# seeeduino_nano.net
KiCad netlist of a schematic drawn in EAGLE
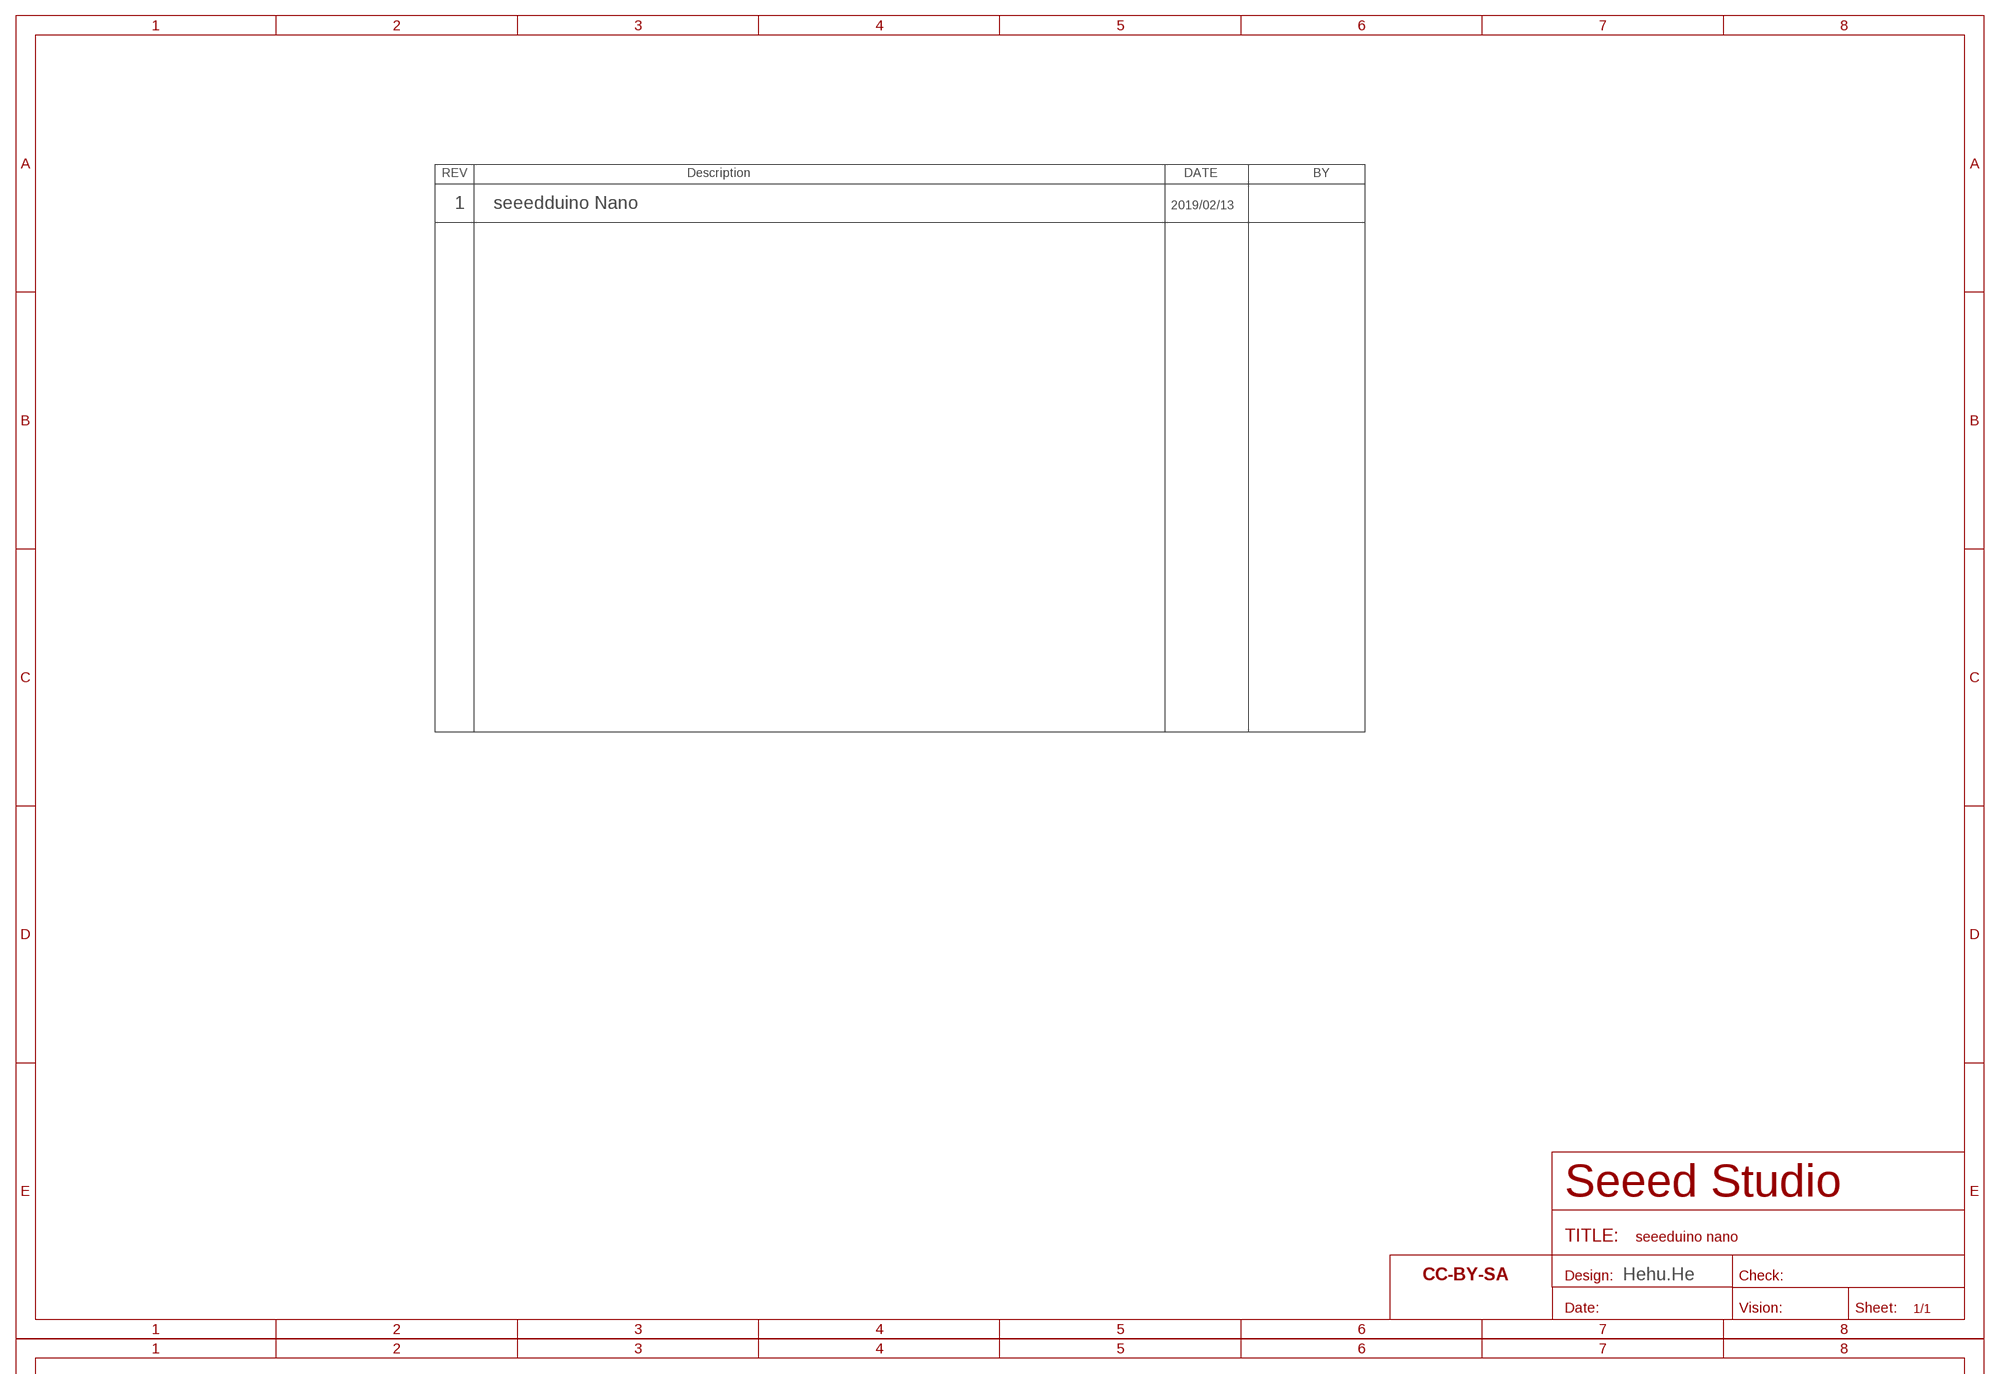
[diagram p0: schematic, sheet 1, part 1 of 2]
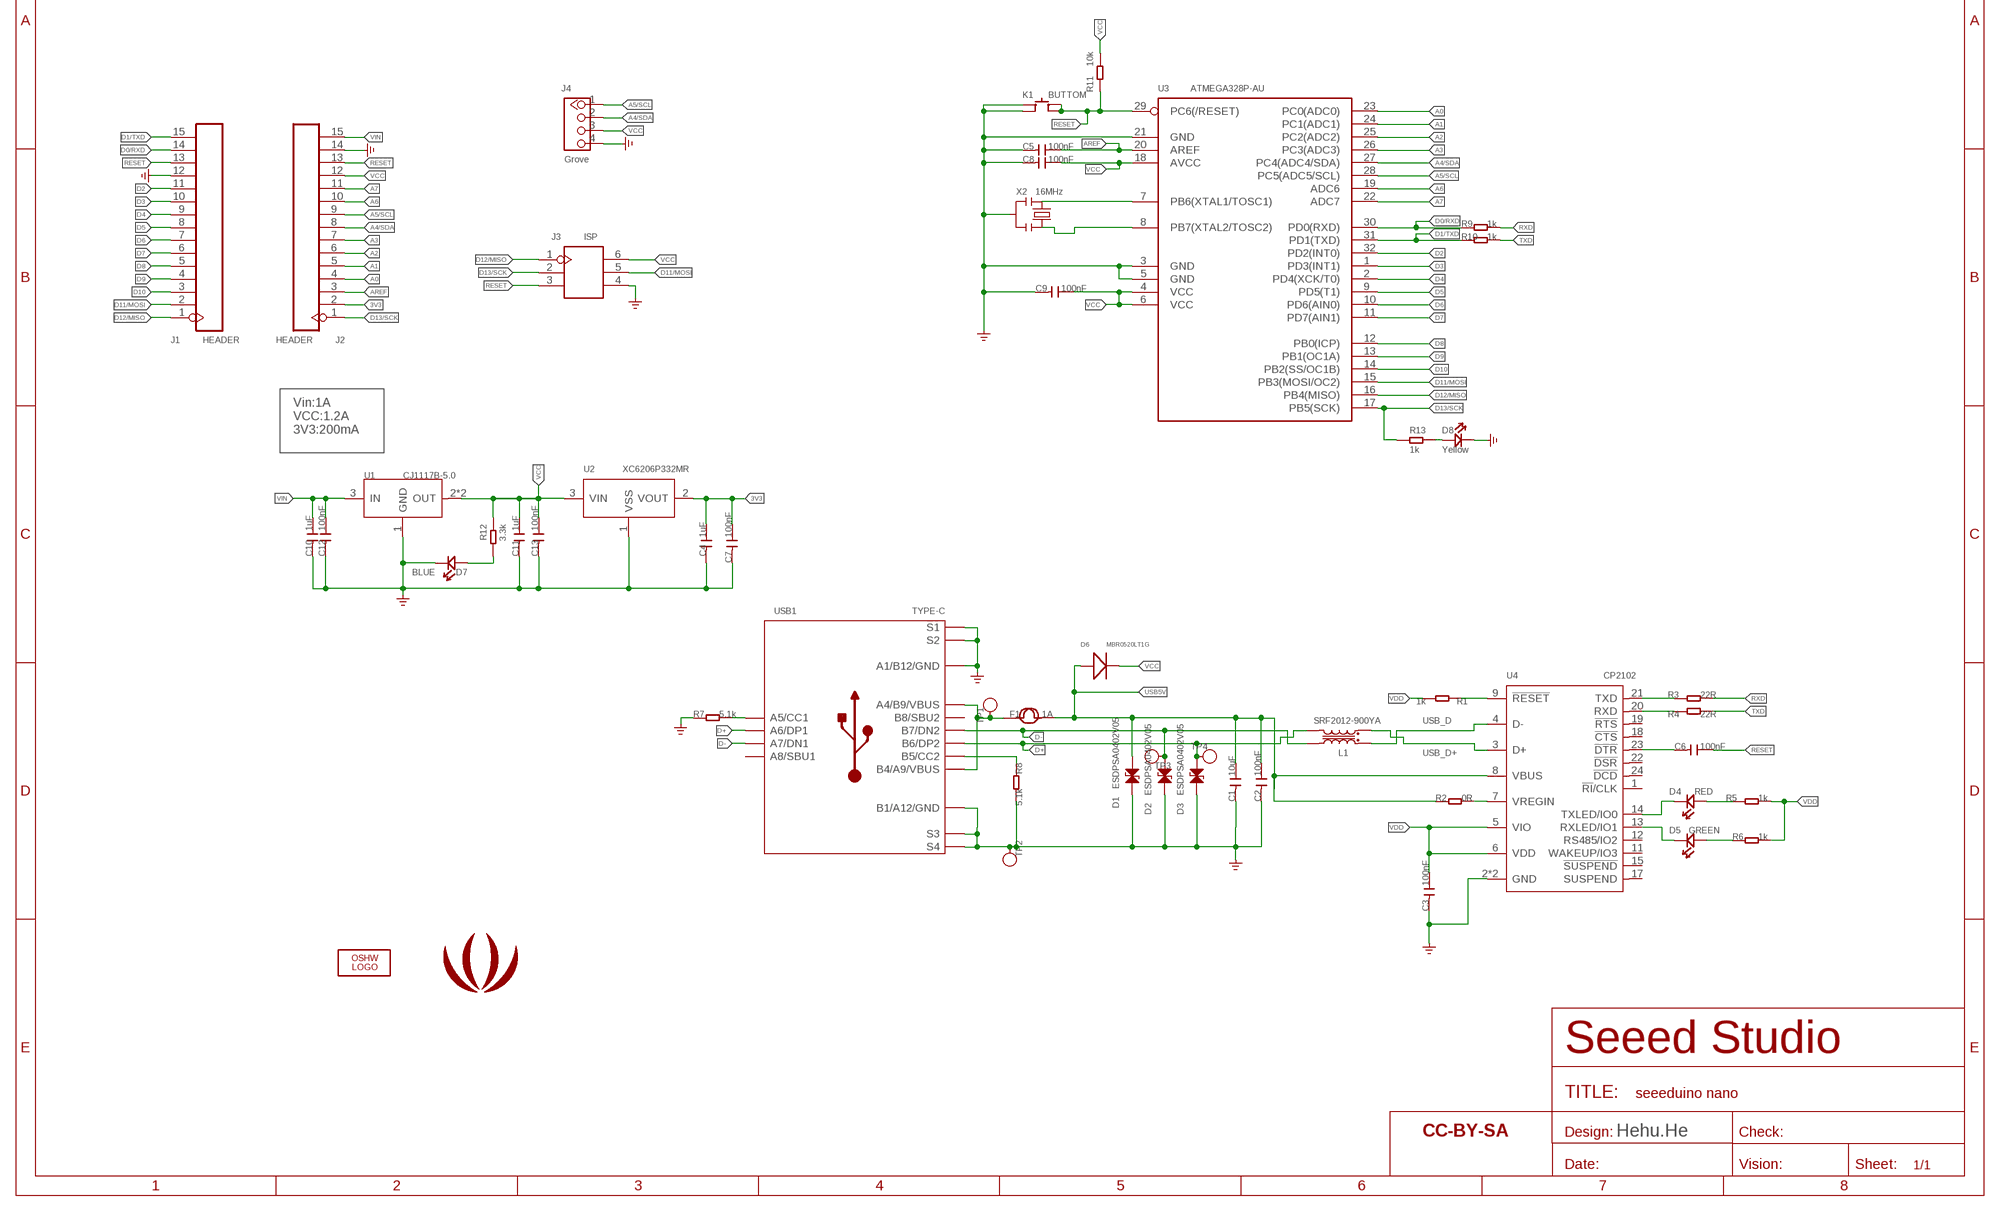
[diagram p1: schematic, sheet 1, part 2 of 2]

(export (version "E")
  (design (tool "Eeschema 10.0.6"))
  (components
    (comp (ref "C1")
      (value "10uF")
      (footprint "eagle-import:C0603")
      (libsource (lib "eagle-import") (part "CAP-0603"))
    )
    (comp (ref "C2")
      (value "100nF")
      (footprint "eagle-import:C0603")
      (libsource (lib "eagle-import") (part "CAP-0603"))
    )
    (comp (ref "C3")
      (value "100nF")
      (footprint "eagle-import:C0603")
      (libsource (lib "eagle-import") (part "C-0603"))
    )
    (comp (ref "C4")
      (value "1uF")
      (footprint "eagle-import:C0603")
      (libsource (lib "eagle-import") (part "C-0603"))
    )
    (comp (ref "C5")
      (value "100nF")
      (footprint "eagle-import:C0603")
      (libsource (lib "eagle-import") (part "C-0603"))
    )
    (comp (ref "C6")
      (value "100nF")
      (footprint "eagle-import:C0603")
      (libsource (lib "eagle-import") (part "C-0603"))
    )
    (comp (ref "C7")
      (value "100nF")
      (footprint "eagle-import:C0603")
      (libsource (lib "eagle-import") (part "C-0603"))
    )
    (comp (ref "C8")
      (value "100nF")
      (footprint "eagle-import:C0603")
      (libsource (lib "eagle-import") (part "C-0603"))
    )
    (comp (ref "C9")
      (value "100nF")
      (footprint "eagle-import:C0603")
      (libsource (lib "eagle-import") (part "C-0603"))
    )
    (comp (ref "C10")
      (value "1uF")
      (footprint "eagle-import:C0603")
      (libsource (lib "eagle-import") (part "C-0603"))
    )
    (comp (ref "C11")
      (value "1uF")
      (footprint "eagle-import:C0603")
      (libsource (lib "eagle-import") (part "C-0603"))
    )
    (comp (ref "C12")
      (value "100nF")
      (footprint "eagle-import:C0603")
      (libsource (lib "eagle-import") (part "C-0603"))
    )
    (comp (ref "C13")
      (value "100nF")
      (footprint "eagle-import:C0603")
      (libsource (lib "eagle-import") (part "C-0603"))
    )
    (comp (ref "D1")
      (value "ESDPSA0402V05")
      (footprint "eagle-import:ESD-0402")
      (libsource (lib "eagle-import") (part "D-ESD-2P-DOUBLE-0402"))
    )
    (comp (ref "D2")
      (value "ESDPSA0402V05")
      (footprint "eagle-import:ESD-0402")
      (libsource (lib "eagle-import") (part "D-ESD-2P-DOUBLE-0402"))
    )
    (comp (ref "D3")
      (value "ESDPSA0402V05")
      (footprint "eagle-import:ESD-0402")
      (libsource (lib "eagle-import") (part "D-ESD-2P-DOUBLE-0402"))
    )
    (comp (ref "D4")
      (value "RED")
      (footprint "eagle-import:LED-0402")
      (libsource (lib "eagle-import") (part "LED-0402"))
    )
    (comp (ref "D5")
      (value "GREEN")
      (footprint "eagle-import:LED-0402")
      (libsource (lib "eagle-import") (part "LED-0402"))
    )
    (comp (ref "D6")
      (value "MBR0520LT1G")
      (footprint "eagle-import:SOD123-2.7X1.6")
      (libsource (lib "eagle-import") (part "D'MBR0520LT1'"))
    )
    (comp (ref "D7")
      (value "BLUE")
      (footprint "eagle-import:LED-0402")
      (libsource (lib "eagle-import") (part "LED-0402"))
    )
    (comp (ref "D8")
      (value "Yellow")
      (footprint "eagle-import:LED-0402")
      (libsource (lib "eagle-import") (part "LED-0402"))
    )
    (comp (ref "F1")
      (value "1A")
      (footprint "eagle-import:F1206")
      (libsource (lib "eagle-import") (part "FUSE'1206'"))
    )
    (comp (ref "J1")
      (value "HEADER")
      (footprint "eagle-import:H15-2.54")
      (libsource (lib "eagle-import") (part "HEADER-15P'2.54'"))
    )
    (comp (ref "J2")
      (value "HEADER")
      (footprint "eagle-import:H15-2.54")
      (libsource (lib "eagle-import") (part "HEADER-15P'2.54'"))
    )
    (comp (ref "J3")
      (value "ISP")
      (footprint "eagle-import:H2X3-2.54")
      (libsource (lib "eagle-import") (part "HEADER-2X3P-2.54"))
    )
    (comp (ref "J4")
      (value "Grove")
      (footprint "eagle-import:HW4-2.0")
      (libsource (lib "eagle-import") (part "GROVE-CONNECTOR-DIP-2.0"))
    )
    (comp (ref "K1")
      (value "BUTTOM")
      (footprint "eagle-import:SW4P-SMD-4.5X3.2X2.5MM")
      (libsource (lib "eagle-import") (part "BUTTON-4P-4.5X3.2"))
    )
    (comp (ref "L1")
      (value "SRF2012-900YA")
      (footprint "eagle-import:INT4-0.85-2X1.25X1.2MM")
      (libsource (lib "eagle-import") (part "INDUCTOR-COMMON-MODE-SRF2012-900YA"))
    )
    (comp (ref "LOGO1")
      (value "LOGO-OSHW-FILLX0100-NT")
      (footprint "eagle-import:OSHW_FILLX100_NOTEXT")
      (fields (field (name "PARTNO") "DNP"))
      (libsource (lib "eagle-import") (part "LOGO-OSHW-FILLX0100-NT"))
    )
    (comp (ref "R1")
      (value "1k")
      (footprint "eagle-import:R0603")
      (libsource (lib "eagle-import") (part "R-0603"))
    )
    (comp (ref "R2")
      (value "0R")
      (footprint "eagle-import:R0603")
      (libsource (lib "eagle-import") (part "R-0603"))
    )
    (comp (ref "R3")
      (value "22R")
      (footprint "eagle-import:R0603")
      (libsource (lib "eagle-import") (part "R-0603"))
    )
    (comp (ref "R4")
      (value "22R")
      (footprint "eagle-import:R0603")
      (libsource (lib "eagle-import") (part "R-0603"))
    )
    (comp (ref "R5")
      (value "1k")
      (footprint "eagle-import:R0603")
      (libsource (lib "eagle-import") (part "R-0603"))
    )
    (comp (ref "R6")
      (value "1k")
      (footprint "eagle-import:R0603")
      (libsource (lib "eagle-import") (part "R-0603"))
    )
    (comp (ref "R7")
      (value "5.1k")
      (footprint "eagle-import:R0603")
      (libsource (lib "eagle-import") (part "R-0603"))
    )
    (comp (ref "R8")
      (value "5.1k")
      (footprint "eagle-import:R0603")
      (libsource (lib "eagle-import") (part "R-0603"))
    )
    (comp (ref "R9")
      (value "1k")
      (footprint "eagle-import:R0603")
      (libsource (lib "eagle-import") (part "R-0603"))
    )
    (comp (ref "R10")
      (value "1k")
      (footprint "eagle-import:R0603")
      (libsource (lib "eagle-import") (part "R-0603"))
    )
    (comp (ref "R11")
      (value "10k")
      (footprint "eagle-import:R0603")
      (libsource (lib "eagle-import") (part "R-0603"))
    )
    (comp (ref "R12")
      (value "3.3k")
      (footprint "eagle-import:R0603")
      (libsource (lib "eagle-import") (part "R-0603"))
    )
    (comp (ref "R13")
      (value "1k")
      (footprint "eagle-import:R0603")
      (libsource (lib "eagle-import") (part "R-0603"))
    )
    (comp (ref "TP1")
      (value "TEST")
      (footprint "eagle-import:TP-D45MIL")
      (fields (field (name "PARTNO") "DNP"))
      (libsource (lib "eagle-import") (part "TEST-POINT'4545'"))
    )
    (comp (ref "TP2")
      (value "TEST")
      (footprint "eagle-import:TP-D45MIL")
      (fields (field (name "PARTNO") "DNP"))
      (libsource (lib "eagle-import") (part "TEST-POINT'4545'"))
    )
    (comp (ref "TP3")
      (value "TEST")
      (footprint "eagle-import:TP-D45MIL")
      (fields (field (name "PARTNO") "DNP"))
      (libsource (lib "eagle-import") (part "TEST-POINT'4545'"))
    )
    (comp (ref "TP4")
      (value "TEST")
      (footprint "eagle-import:TP-D45MIL")
      (fields (field (name "PARTNO") "DNP"))
      (libsource (lib "eagle-import") (part "TEST-POINT'4545'"))
    )
    (comp (ref "U$2")
      (value "LOGO-SEEED-SMALL-SILK")
      (footprint "eagle-import:SEEED-SILK--TNAME-160_153MIL")
      (fields (field (name "PARTNO") "DNP"))
      (libsource (lib "eagle-import") (part "LOGO-SEEED-SMALL-SILK"))
    )
    (comp (ref "U1")
      (value "CJ1117B-5.0")
      (footprint "eagle-import:SOT-223")
      (libsource (lib "eagle-import") (part "PMIC-CJ1117S"))
    )
    (comp (ref "U2")
      (value "XC6206P332MR")
      (footprint "eagle-import:SOT-23")
      (libsource (lib "eagle-import") (part "PMIC-XC6206PMR"))
    )
    (comp (ref "U3")
      (value "ATMEGA328P-AU")
      (footprint "eagle-import:TQFP32-0.8-7X7MM")
      (libsource (lib "eagle-import") (part "MCU-ATMEGA8/168/328'AU'"))
    )
    (comp (ref "U4")
      (value "CP2102")
      (footprint "eagle-import:QFN24G-0.5-4X4MM")
      (libsource (lib "eagle-import") (part "CONVERTER-CP2102N(QFN24)"))
    )
    (comp (ref "USB1")
      (value "TYPE-C")
      (footprint "eagle-import:USB2.0-TYPE-C")
      (libsource (lib "eagle-import") (part "USB2.0-TYPE-C"))
    )
    (comp (ref "X2")
      (value "16MHz")
      (footprint "eagle-import:RESONATOR3-SMD-3.6X1.3X0.8MM")
      (libsource (lib "eagle-import") (part "CRYSTAL-RESONATOR"))
    )
  )
  (nets
    (net (code "1") (name "/USB_D") (class "Default")
      (node (ref "L1") (pin "1") (pinfunction "1_1") (pintype "bidirectional"))
      (node (ref "U4") (pin "4") (pinfunction "D-_4") (pintype "bidirectional"))
    )
    (net (code "2") (name "/USB_D+") (class "Default")
      (node (ref "L1") (pin "4") (pinfunction "4_4") (pintype "bidirectional"))
      (node (ref "U4") (pin "3") (pinfunction "D+_3") (pintype "bidirectional"))
    )
    (net (code "3") (name "3V3") (class "Default")
      (node (ref "C4") (pin "1") (pinfunction "1_1") (pintype "passive"))
      (node (ref "C7") (pin "1") (pinfunction "1_1") (pintype "passive"))
      (node (ref "J2") (pin "2") (pinfunction "2_2") (pintype "passive"))
      (node (ref "U2") (pin "2") (pinfunction "VOUT_2") (pintype "bidirectional"))
    )
    (net (code "4") (name "A0") (class "Default")
      (node (ref "J2") (pin "4") (pinfunction "4_4") (pintype "passive"))
      (node (ref "U3") (pin "23") (pinfunction "PC0(ADC0)_23") (pintype "bidirectional"))
    )
    (net (code "5") (name "A1") (class "Default")
      (node (ref "J2") (pin "5") (pinfunction "5_5") (pintype "passive"))
      (node (ref "U3") (pin "24") (pinfunction "PC1(ADC1)_24") (pintype "bidirectional"))
    )
    (net (code "6") (name "A2") (class "Default")
      (node (ref "J2") (pin "6") (pinfunction "6_6") (pintype "passive"))
      (node (ref "U3") (pin "25") (pinfunction "PC2(ADC2)_25") (pintype "bidirectional"))
    )
    (net (code "7") (name "A3") (class "Default")
      (node (ref "J2") (pin "7") (pinfunction "7_7") (pintype "passive"))
      (node (ref "U3") (pin "26") (pinfunction "PC3(ADC3)_26") (pintype "bidirectional"))
    )
    (net (code "8") (name "A4{slash}SDA") (class "Default")
      (node (ref "J2") (pin "8") (pinfunction "8_8") (pintype "passive"))
      (node (ref "J4") (pin "2") (pinfunction "2_2") (pintype "bidirectional"))
      (node (ref "U3") (pin "27") (pinfunction "PC4(ADC4/SDA)_27") (pintype "bidirectional"))
    )
    (net (code "9") (name "A5{slash}SCL") (class "Default")
      (node (ref "J2") (pin "9") (pinfunction "9_9") (pintype "passive"))
      (node (ref "J4") (pin "1") (pinfunction "1_1") (pintype "bidirectional"))
      (node (ref "U3") (pin "28") (pinfunction "PC5(ADC5/SCL)_28") (pintype "bidirectional"))
    )
    (net (code "10") (name "A6") (class "Default")
      (node (ref "J2") (pin "10") (pinfunction "10_10") (pintype "passive"))
      (node (ref "U3") (pin "19") (pinfunction "ADC6_19") (pintype "bidirectional"))
    )
    (net (code "11") (name "A7") (class "Default")
      (node (ref "J2") (pin "11") (pinfunction "11_11") (pintype "passive"))
      (node (ref "U3") (pin "22") (pinfunction "ADC7_22") (pintype "bidirectional"))
    )
    (net (code "12") (name "AREF") (class "Default")
      (node (ref "C5") (pin "1") (pinfunction "1_1") (pintype "passive"))
      (node (ref "J2") (pin "3") (pinfunction "3_3") (pintype "passive"))
      (node (ref "U3") (pin "20") (pinfunction "AREF_20") (pintype "bidirectional"))
    )
    (net (code "13") (name "D+") (class "Default")
      (node (ref "D3") (pin "2") (pinfunction "2_2") (pintype "bidirectional"))
      (node (ref "L1") (pin "3") (pinfunction "3_3") (pintype "bidirectional"))
      (node (ref "TP4") (pin "T") (pinfunction "T_T") (pintype "bidirectional"))
      (node (ref "USB1") (pin "A6") (pinfunction "A6/DP1_A6") (pintype "bidirectional"))
      (node (ref "USB1") (pin "B6") (pinfunction "B6/DP2_B6") (pintype "bidirectional"))
    )
    (net (code "14") (name "D-") (class "Default")
      (node (ref "D2") (pin "2") (pinfunction "2_2") (pintype "bidirectional"))
      (node (ref "L1") (pin "2") (pinfunction "2_2") (pintype "bidirectional"))
      (node (ref "TP3") (pin "T") (pinfunction "T_T") (pintype "bidirectional"))
      (node (ref "USB1") (pin "A7") (pinfunction "A7/DN1_A7") (pintype "bidirectional"))
      (node (ref "USB1") (pin "B7") (pinfunction "B7/DN2_B7") (pintype "bidirectional"))
    )
    (net (code "15") (name "D0{slash}RXD") (class "Default")
      (node (ref "J1") (pin "14") (pinfunction "14_14") (pintype "passive"))
      (node (ref "R9") (pin "1") (pinfunction "1_1") (pintype "passive"))
      (node (ref "U3") (pin "30") (pinfunction "PD0(RXD)_30") (pintype "bidirectional"))
    )
    (net (code "16") (name "D1{slash}TXD") (class "Default")
      (node (ref "J1") (pin "15") (pinfunction "15_15") (pintype "passive"))
      (node (ref "R10") (pin "1") (pinfunction "1_1") (pintype "passive"))
      (node (ref "U3") (pin "31") (pinfunction "PD1(TXD)_31") (pintype "bidirectional"))
    )
    (net (code "17") (name "D2") (class "Default")
      (node (ref "J1") (pin "11") (pinfunction "11_11") (pintype "passive"))
      (node (ref "U3") (pin "32") (pinfunction "PD2(INT0)_32") (pintype "bidirectional"))
    )
    (net (code "18") (name "D3") (class "Default")
      (node (ref "J1") (pin "10") (pinfunction "10_10") (pintype "passive"))
      (node (ref "U3") (pin "1") (pinfunction "PD3(INT1)_1") (pintype "bidirectional"))
    )
    (net (code "19") (name "D4") (class "Default")
      (node (ref "J1") (pin "9") (pinfunction "9_9") (pintype "passive"))
      (node (ref "U3") (pin "2") (pinfunction "PD4(XCK/T0)_2") (pintype "bidirectional"))
    )
    (net (code "20") (name "D5") (class "Default")
      (node (ref "J1") (pin "8") (pinfunction "8_8") (pintype "passive"))
      (node (ref "U3") (pin "9") (pinfunction "PD5(T1)_9") (pintype "bidirectional"))
    )
    (net (code "21") (name "D6") (class "Default")
      (node (ref "J1") (pin "7") (pinfunction "7_7") (pintype "passive"))
      (node (ref "U3") (pin "10") (pinfunction "PD6(AIN0)_10") (pintype "bidirectional"))
    )
    (net (code "22") (name "D7") (class "Default")
      (node (ref "J1") (pin "6") (pinfunction "6_6") (pintype "passive"))
      (node (ref "U3") (pin "11") (pinfunction "PD7(AIN1)_11") (pintype "bidirectional"))
    )
    (net (code "23") (name "D8") (class "Default")
      (node (ref "J1") (pin "5") (pinfunction "5_5") (pintype "passive"))
      (node (ref "U3") (pin "12") (pinfunction "PB0(ICP)_12") (pintype "bidirectional"))
    )
    (net (code "24") (name "D9") (class "Default")
      (node (ref "J1") (pin "4") (pinfunction "4_4") (pintype "passive"))
      (node (ref "U3") (pin "13") (pinfunction "PB1(OC1A)_13") (pintype "bidirectional"))
    )
    (net (code "25") (name "D10") (class "Default")
      (node (ref "J1") (pin "3") (pinfunction "3_3") (pintype "passive"))
      (node (ref "U3") (pin "14") (pinfunction "PB2(SS/OC1B)_14") (pintype "bidirectional"))
    )
    (net (code "26") (name "D11{slash}MOSI") (class "Default")
      (node (ref "J1") (pin "2") (pinfunction "2_2") (pintype "passive"))
      (node (ref "J3") (pin "5") (pinfunction "5_5") (pintype "bidirectional"))
      (node (ref "U3") (pin "15") (pinfunction "PB3(MOSI/OC2)_15") (pintype "bidirectional"))
    )
    (net (code "27") (name "D12{slash}MISO") (class "Default")
      (node (ref "J1") (pin "1") (pinfunction "1_1") (pintype "passive"))
      (node (ref "J3") (pin "1") (pinfunction "1_1") (pintype "bidirectional"))
      (node (ref "U3") (pin "16") (pinfunction "PB4(MISO)_16") (pintype "bidirectional"))
    )
    (net (code "28") (name "D13{slash}SCK") (class "Default")
      (node (ref "J2") (pin "1") (pinfunction "1_1") (pintype "passive"))
      (node (ref "J3") (pin "2") (pinfunction "2_2") (pintype "bidirectional"))
      (node (ref "R13") (pin "1") (pinfunction "1_1") (pintype "passive"))
      (node (ref "U3") (pin "17") (pinfunction "PB5(SCK)_17") (pintype "bidirectional"))
    )
    (net (code "29") (name "GND_POWER") (class "Default")
      (node (ref "C1") (pin "2") (pinfunction "2_2") (pintype "passive"))
      (node (ref "C10") (pin "2") (pinfunction "2_2") (pintype "passive"))
      (node (ref "C11") (pin "2") (pinfunction "2_2") (pintype "passive"))
      (node (ref "C12") (pin "2") (pinfunction "2_2") (pintype "passive"))
      (node (ref "C13") (pin "2") (pinfunction "2_2") (pintype "passive"))
      (node (ref "C2") (pin "2") (pinfunction "2_2") (pintype "passive"))
      (node (ref "C3") (pin "2") (pinfunction "2_2") (pintype "passive"))
      (node (ref "C4") (pin "2") (pinfunction "2_2") (pintype "passive"))
      (node (ref "C5") (pin "2") (pinfunction "2_2") (pintype "passive"))
      (node (ref "C7") (pin "2") (pinfunction "2_2") (pintype "passive"))
      (node (ref "C8") (pin "2") (pinfunction "2_2") (pintype "passive"))
      (node (ref "C9") (pin "2") (pinfunction "2_2") (pintype "passive"))
      (node (ref "D1") (pin "1") (pinfunction "1_1") (pintype "bidirectional"))
      (node (ref "D2") (pin "1") (pinfunction "1_1") (pintype "bidirectional"))
      (node (ref "D3") (pin "1") (pinfunction "1_1") (pintype "bidirectional"))
      (node (ref "D7") (pin "-") (pinfunction "-_-") (pintype "passive"))
      (node (ref "D8") (pin "-") (pinfunction "-_-") (pintype "passive"))
      (node (ref "J1") (pin "12") (pinfunction "12_12") (pintype "passive"))
      (node (ref "J2") (pin "14") (pinfunction "14_14") (pintype "passive"))
      (node (ref "J3") (pin "4") (pinfunction "4_4") (pintype "bidirectional"))
      (node (ref "J4") (pin "4") (pinfunction "4_4") (pintype "bidirectional"))
      (node (ref "K1") (pin "1") (pinfunction "A0_1") (pintype "bidirectional"))
      (node (ref "K1") (pin "2") (pinfunction "A1_2") (pintype "bidirectional"))
      (node (ref "R7") (pin "1") (pinfunction "1_1") (pintype "passive"))
      (node (ref "R8") (pin "2") (pinfunction "2_2") (pintype "passive"))
      (node (ref "TP2") (pin "T") (pinfunction "T_T") (pintype "bidirectional"))
      (node (ref "U1") (pin "1") (pinfunction "GND_1") (pintype "bidirectional"))
      (node (ref "U2") (pin "1") (pinfunction "VSS_1") (pintype "bidirectional"))
      (node (ref "U3") (pin "21") (pinfunction "GND_21") (pintype "bidirectional"))
      (node (ref "U3") (pin "3") (pinfunction "GND_3") (pintype "bidirectional"))
      (node (ref "U3") (pin "5") (pinfunction "GND_5") (pintype "bidirectional"))
      (node (ref "U4") (pin "2") (pinfunction "GND_2") (pintype "bidirectional"))
      (node (ref "U4") (pin "PAD") (pinfunction "GND_PAD") (pintype "bidirectional"))
      (node (ref "USB1") (pin "A1_B12") (pinfunction "A1/B12/GND_A1_B12") (pintype "bidirectional"))
      (node (ref "USB1") (pin "B1_A12") (pinfunction "B1/A12/GND_B1_A12") (pintype "bidirectional"))
      (node (ref "USB1") (pin "S1") (pinfunction "S1_S1") (pintype "bidirectional"))
      (node (ref "USB1") (pin "S2") (pinfunction "S2_S2") (pintype "bidirectional"))
      (node (ref "USB1") (pin "S3") (pinfunction "S3_S3") (pintype "bidirectional"))
      (node (ref "USB1") (pin "S4") (pinfunction "S4_S4") (pintype "bidirectional"))
      (node (ref "USB1") (pin "S5") (pinfunction "S1_S5") (pintype "bidirectional"))
      (node (ref "USB1") (pin "S6") (pinfunction "S2_S6") (pintype "bidirectional"))
      (node (ref "X2") (pin "2") (pinfunction "2_2") (pintype "passive"))
    )
    (net (code "30") (name "Net-(D4-Pad+)") (class "Default")
      (node (ref "D4") (pin "+") (pinfunction "+_+") (pintype "passive"))
      (node (ref "R5") (pin "1") (pinfunction "1_1") (pintype "passive"))
    )
    (net (code "31") (name "Net-(D5-Pad+)") (class "Default")
      (node (ref "D5") (pin "+") (pinfunction "+_+") (pintype "passive"))
      (node (ref "R6") (pin "1") (pinfunction "1_1") (pintype "passive"))
    )
    (net (code "32") (name "Net-(D7-Pad+)") (class "Default")
      (node (ref "D7") (pin "+") (pinfunction "+_+") (pintype "passive"))
      (node (ref "R12") (pin "2") (pinfunction "2_2") (pintype "passive"))
    )
    (net (code "33") (name "Net-(D8-Pad+)") (class "Default")
      (node (ref "D8") (pin "+") (pinfunction "+_+") (pintype "passive"))
      (node (ref "R13") (pin "2") (pinfunction "2_2") (pintype "passive"))
    )
    (net (code "34") (name "Net-(U3-PB6(XTAL1{slash}TOSC1))") (class "Default")
      (node (ref "U3") (pin "7") (pinfunction "PB6(XTAL1/TOSC1)_7") (pintype "bidirectional"))
      (node (ref "X2") (pin "1") (pinfunction "1_1") (pintype "passive"))
    )
    (net (code "35") (name "Net-(U3-PB7(XTAL2{slash}TOSC2))") (class "Default")
      (node (ref "U3") (pin "8") (pinfunction "PB7(XTAL2/TOSC2)_8") (pintype "bidirectional"))
      (node (ref "X2") (pin "3") (pinfunction "3_3") (pintype "passive"))
    )
    (net (code "36") (name "Net-(U4-RXD)") (class "Default")
      (node (ref "R4") (pin "1") (pinfunction "1_1") (pintype "passive"))
      (node (ref "U4") (pin "20") (pinfunction "RXD_20") (pintype "bidirectional"))
    )
    (net (code "37") (name "Net-(U4-RXLED{slash}IO1)") (class "Default")
      (node (ref "D5") (pin "-") (pinfunction "-_-") (pintype "passive"))
      (node (ref "U4") (pin "13") (pinfunction "RXLED/IO1_13") (pintype "bidirectional"))
    )
    (net (code "38") (name "Net-(U4-TXD)") (class "Default")
      (node (ref "R3") (pin "1") (pinfunction "1_1") (pintype "passive"))
      (node (ref "U4") (pin "21") (pinfunction "TXD_21") (pintype "bidirectional"))
    )
    (net (code "39") (name "Net-(U4-TXLED{slash}IO0)") (class "Default")
      (node (ref "D4") (pin "-") (pinfunction "-_-") (pintype "passive"))
      (node (ref "U4") (pin "14") (pinfunction "TXLED/IO0_14") (pintype "bidirectional"))
    )
    (net (code "40") (name "Net-(U4-VREGIN)") (class "Default")
      (node (ref "R2") (pin "2") (pinfunction "2_2") (pintype "passive"))
      (node (ref "U4") (pin "7") (pinfunction "VREGIN_7") (pintype "bidirectional"))
    )
    (net (code "41") (name "Net-(U4-~{DTR})") (class "Default")
      (node (ref "C6") (pin "2") (pinfunction "2_2") (pintype "passive"))
      (node (ref "U4") (pin "23") (pinfunction "~{DTR}_23") (pintype "bidirectional"))
    )
    (net (code "42") (name "Net-(U4-~{RESET})") (class "Default")
      (node (ref "R1") (pin "2") (pinfunction "2_2") (pintype "passive"))
      (node (ref "U4") (pin "9") (pinfunction "~{RESET}_9") (pintype "bidirectional"))
    )
    (net (code "43") (name "Net-(USB1-A4{slash}B9{slash}VBUS)") (class "Default")
      (node (ref "F1") (pin "1") (pinfunction "1_1") (pintype "bidirectional"))
      (node (ref "TP1") (pin "T") (pinfunction "T_T") (pintype "bidirectional"))
      (node (ref "USB1") (pin "A4_B9") (pinfunction "A4/B9/VBUS_A4_B9") (pintype "bidirectional"))
      (node (ref "USB1") (pin "B4_A9") (pinfunction "B4/A9/VBUS_B4_A9") (pintype "bidirectional"))
    )
    (net (code "44") (name "Net-(USB1-A5{slash}CC1)") (class "Default")
      (node (ref "R7") (pin "2") (pinfunction "2_2") (pintype "passive"))
      (node (ref "USB1") (pin "A5") (pinfunction "A5/CC1_A5") (pintype "bidirectional"))
    )
    (net (code "45") (name "Net-(USB1-B5{slash}CC2)") (class "Default")
      (node (ref "R8") (pin "1") (pinfunction "1_1") (pintype "passive"))
      (node (ref "USB1") (pin "B5") (pinfunction "B5/CC2_B5") (pintype "bidirectional"))
    )
    (net (code "46") (name "RESET") (class "Default")
      (node (ref "C6") (pin "1") (pinfunction "1_1") (pintype "passive"))
      (node (ref "J1") (pin "13") (pinfunction "13_13") (pintype "passive"))
      (node (ref "J2") (pin "13") (pinfunction "13_13") (pintype "passive"))
      (node (ref "J3") (pin "3") (pinfunction "3_3") (pintype "bidirectional"))
      (node (ref "K1") (pin "3") (pinfunction "B0_3") (pintype "bidirectional"))
      (node (ref "K1") (pin "4") (pinfunction "B1_4") (pintype "bidirectional"))
      (node (ref "R11") (pin "1") (pinfunction "1_1") (pintype "passive"))
      (node (ref "U3") (pin "29") (pinfunction "PC6(/RESET)_29") (pintype "bidirectional"))
    )
    (net (code "47") (name "RXD") (class "Default")
      (node (ref "R3") (pin "2") (pinfunction "2_2") (pintype "passive"))
      (node (ref "R9") (pin "2") (pinfunction "2_2") (pintype "passive"))
    )
    (net (code "48") (name "TXD") (class "Default")
      (node (ref "R10") (pin "2") (pinfunction "2_2") (pintype "passive"))
      (node (ref "R4") (pin "2") (pinfunction "2_2") (pintype "passive"))
    )
    (net (code "49") (name "USB5V") (class "Default")
      (node (ref "C1") (pin "1") (pinfunction "1_1") (pintype "passive"))
      (node (ref "C2") (pin "1") (pinfunction "1_1") (pintype "passive"))
      (node (ref "D1") (pin "2") (pinfunction "2_2") (pintype "bidirectional"))
      (node (ref "D6") (pin "1") (pinfunction "+_1") (pintype "passive"))
      (node (ref "F1") (pin "2") (pinfunction "2_2") (pintype "bidirectional"))
      (node (ref "R2") (pin "1") (pinfunction "1_1") (pintype "passive"))
      (node (ref "U4") (pin "8") (pinfunction "VBUS_8") (pintype "bidirectional"))
    )
    (net (code "50") (name "VCC") (class "Default")
      (node (ref "C11") (pin "1") (pinfunction "1_1") (pintype "passive"))
      (node (ref "C13") (pin "1") (pinfunction "1_1") (pintype "passive"))
      (node (ref "C8") (pin "1") (pinfunction "1_1") (pintype "passive"))
      (node (ref "C9") (pin "1") (pinfunction "1_1") (pintype "passive"))
      (node (ref "D6") (pin "2") (pinfunction "-_2") (pintype "passive"))
      (node (ref "J2") (pin "12") (pinfunction "12_12") (pintype "passive"))
      (node (ref "J3") (pin "6") (pinfunction "6_6") (pintype "bidirectional"))
      (node (ref "J4") (pin "3") (pinfunction "3_3") (pintype "bidirectional"))
      (node (ref "R11") (pin "2") (pinfunction "2_2") (pintype "passive"))
      (node (ref "R12") (pin "1") (pinfunction "1_1") (pintype "passive"))
      (node (ref "U1") (pin "2") (pinfunction "OUT_2") (pintype "bidirectional"))
      (node (ref "U1") (pin "TER") (pinfunction "OUT_TER") (pintype "bidirectional"))
      (node (ref "U2") (pin "3") (pinfunction "VIN_3") (pintype "bidirectional"))
      (node (ref "U3") (pin "18") (pinfunction "AVCC_18") (pintype "bidirectional"))
      (node (ref "U3") (pin "4") (pinfunction "VCC_4") (pintype "bidirectional"))
      (node (ref "U3") (pin "6") (pinfunction "VCC_6") (pintype "bidirectional"))
    )
    (net (code "51") (name "VDD") (class "Default")
      (node (ref "C3") (pin "1") (pinfunction "1_1") (pintype "passive"))
      (node (ref "R1") (pin "1") (pinfunction "1_1") (pintype "passive"))
      (node (ref "R5") (pin "2") (pinfunction "2_2") (pintype "passive"))
      (node (ref "R6") (pin "2") (pinfunction "2_2") (pintype "passive"))
      (node (ref "U4") (pin "5") (pinfunction "VIO_5") (pintype "bidirectional"))
      (node (ref "U4") (pin "6") (pinfunction "VDD_6") (pintype "bidirectional"))
    )
    (net (code "52") (name "VIN") (class "Default")
      (node (ref "C10") (pin "1") (pinfunction "1_1") (pintype "passive"))
      (node (ref "C12") (pin "1") (pinfunction "1_1") (pintype "passive"))
      (node (ref "J2") (pin "15") (pinfunction "15_15") (pintype "passive"))
      (node (ref "U1") (pin "3") (pinfunction "IN_3") (pintype "bidirectional"))
    )
    (net (code "53") (name "unconnected-(U4-RS485{slash}IO2-Pad12)") (class "Default")
      (node (ref "U4") (pin "12") (pinfunction "RS485/IO2_12") (pintype "bidirectional"))
    )
    (net (code "54") (name "unconnected-(U4-SUSPEND-Pad17)") (class "Default")
      (node (ref "U4") (pin "17") (pinfunction "SUSPEND_17") (pintype "bidirectional"))
    )
    (net (code "55") (name "unconnected-(U4-WAKEUP{slash}IO3-Pad11)") (class "Default")
      (node (ref "U4") (pin "11") (pinfunction "WAKEUP/IO3_11") (pintype "bidirectional"))
    )
    (net (code "56") (name "unconnected-(U4-~{CTS}-Pad18)") (class "Default")
      (node (ref "U4") (pin "18") (pinfunction "~{CTS}_18") (pintype "bidirectional"))
    )
    (net (code "57") (name "unconnected-(U4-~{DCD}-Pad24)") (class "Default")
      (node (ref "U4") (pin "24") (pinfunction "~{DCD}_24") (pintype "bidirectional"))
    )
    (net (code "58") (name "unconnected-(U4-~{DSR}-Pad22)") (class "Default")
      (node (ref "U4") (pin "22") (pinfunction "~{DSR}_22") (pintype "bidirectional"))
    )
    (net (code "59") (name "unconnected-(U4-~{RI}{slash}CLK-Pad1)") (class "Default")
      (node (ref "U4") (pin "1") (pinfunction "~{RI}/CLK_1") (pintype "bidirectional"))
    )
    (net (code "60") (name "unconnected-(U4-~{RTS}-Pad19)") (class "Default")
      (node (ref "U4") (pin "19") (pinfunction "~{RTS}_19") (pintype "bidirectional"))
    )
    (net (code "61") (name "unconnected-(U4-~{SUSPEND}-Pad15)") (class "Default")
      (node (ref "U4") (pin "15") (pinfunction "~{SUSPEND}_15") (pintype "bidirectional"))
    )
    (net (code "62") (name "unconnected-(USB1-A8{slash}SBU1-PadA8)") (class "Default")
      (node (ref "USB1") (pin "A8") (pinfunction "A8/SBU1_A8") (pintype "bidirectional"))
    )
    (net (code "63") (name "unconnected-(USB1-B8{slash}SBU2-PadB8)") (class "Default")
      (node (ref "USB1") (pin "B8") (pinfunction "B8/SBU2_B8") (pintype "bidirectional"))
    )
  )
)
